# BatteryPack.net
KiCad netlist of a schematic drawn in Altium Designer
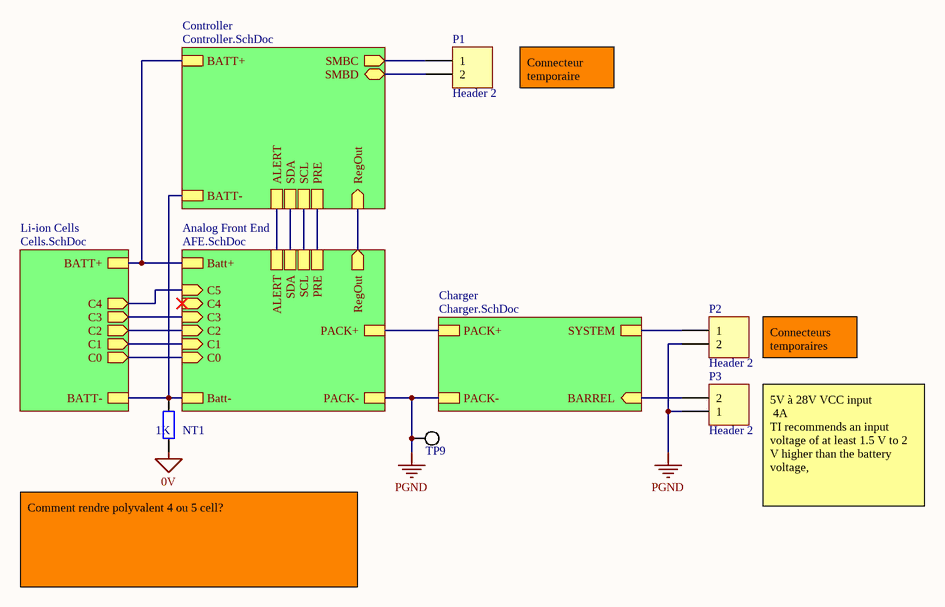
[diagram p0: BatteryPack.SchDoc]

(export (version "E")
  (design (tool "Eeschema 10.0.6"))
  (components
    (comp (ref "NT1")
      (value "1K")
      (footprint "AXIAL-0.4")
      (description "Resistor")
      (fields (field (name "Comment") "Res2") (field (name "PUBLISHER") "Altium Limited"))
      (libsource (lib "Miscellaneous Devices") (part "Res2"))
    )
    (comp (ref "P1")
      (value "Header 2")
      (footprint "HDR1X2")
      (description "Header, 2-Pin")
      (fields (field (name "PUBLISHER") "Altium Limited"))
      (libsource (lib "") (part "Header 2_1"))
    )
    (comp (ref "P2")
      (value "Header 2")
      (footprint "HDR1X2")
      (description "Header, 2-Pin")
      (fields (field (name "PUBLISHER") "Altium Limited"))
      (libsource (lib "") (part "Header 2_1"))
    )
    (comp (ref "P3")
      (value "Header 2")
      (footprint "HDR1X2")
      (description "Header, 2-Pin")
      (fields (field (name "PUBLISHER") "Altium Limited"))
      (libsource (lib "Miscellaneous Connectors") (part "Header 2"))
    )
    (comp (ref "TP9")
      (value "testpoint")
      (footprint "0805 testpoint")
      (description "Testpoint")
      (libsource (lib "BlocBatteries") (part "testpoint"))
    )
  )
  (nets
    (net (code "2") (name "/BARREL") (class "Default")
      (node (ref "P3") (pin "2") (pinfunction "2_2") (pintype "passive"))
    )
    (net (code "4") (name "/BATT-") (class "Default")
      (node (ref "NT1") (pin "2") (pinfunction "2_2") (pintype "passive"))
    )
    (net (code "16") (name "/SMBC") (class "Default")
      (node (ref "P1") (pin "1") (pinfunction "1_1") (pintype "passive"))
    )
    (net (code "17") (name "/SMBD") (class "Default")
      (node (ref "P1") (pin "2") (pinfunction "2_2") (pintype "passive"))
    )
    (net (code "18") (name "/SYSTEM") (class "Default")
      (node (ref "P2") (pin "1") (pinfunction "1_1") (pintype "passive"))
    )
    (net (code "19") (name "0V") (class "Default")
      (node (ref "NT1") (pin "1") (pinfunction "1_1") (pintype "passive"))
    )
    (net (code "20") (name "PGND") (class "Default")
      (node (ref "P2") (pin "2") (pinfunction "2_2") (pintype "passive"))
      (node (ref "P3") (pin "1") (pinfunction "1_1") (pintype "passive"))
      (node (ref "TP9") (pin "1") (pinfunction "1_1") (pintype "passive"))
    )
  )
)
